# LoRa_Plug.net
KiCad netlist of a schematic drawn in EAGLE
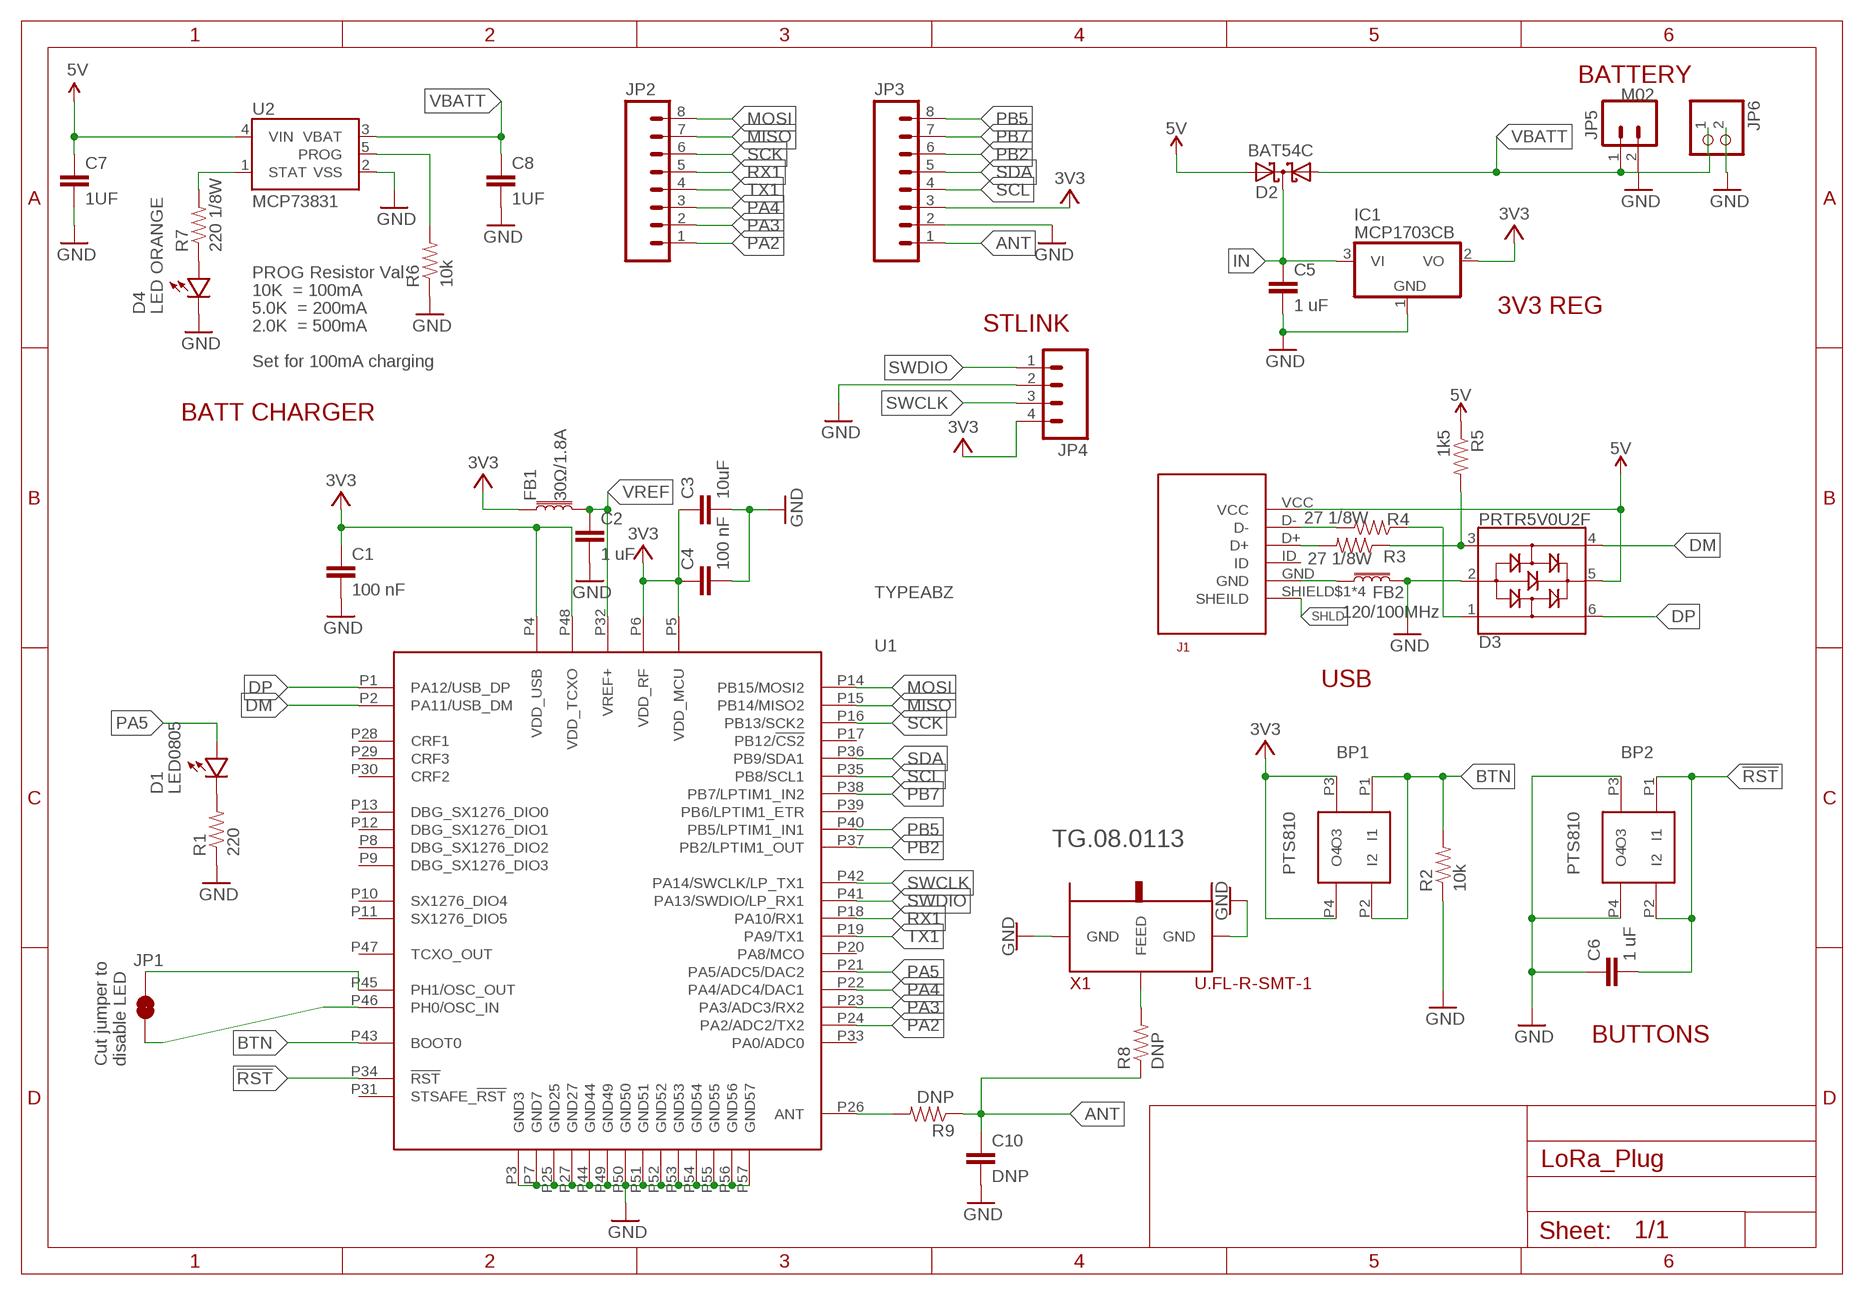
[diagram p0: schematic, sheet 1]

(export (version "E")
  (design (tool "Eeschema 10.0.6"))
  (components
    (comp (ref "BP1")
      (value "PTS810")
      (footprint "eagle-import:C&KTACTILESWITCH")
      (libsource (lib "eagle-import") (part "C&KTACTILESWITCH"))
    )
    (comp (ref "BP2")
      (value "PTS810")
      (footprint "eagle-import:C&KTACTILESWITCH")
      (libsource (lib "eagle-import") (part "C&KTACTILESWITCH"))
    )
    (comp (ref "C1")
      (value "100 nF")
      (footprint "eagle-import:0603-CAP")
      (libsource (lib "eagle-import") (part "CAP0603-CAP"))
    )
    (comp (ref "C2")
      (value "1 uF")
      (footprint "eagle-import:0603-CAP")
      (libsource (lib "eagle-import") (part "CAP0603-CAP"))
    )
    (comp (ref "C3")
      (value "10uF")
      (footprint "eagle-import:0603-CAP")
      (libsource (lib "eagle-import") (part "CAP0603-CAP"))
    )
    (comp (ref "C4")
      (value "100 nF")
      (footprint "eagle-import:0603-CAP")
      (libsource (lib "eagle-import") (part "CAP0603-CAP"))
    )
    (comp (ref "C5")
      (value "1 uF")
      (footprint "eagle-import:0603-CAP")
      (libsource (lib "eagle-import") (part "CAP0603-CAP"))
    )
    (comp (ref "C6")
      (value "1 uF")
      (footprint "eagle-import:0603-CAP")
      (libsource (lib "eagle-import") (part "CAP0603-CAP"))
    )
    (comp (ref "C7")
      (value "1UF")
      (footprint "eagle-import:0603-CAP")
      (libsource (lib "eagle-import") (part "CAP0603-CAP"))
    )
    (comp (ref "C8")
      (value "1UF")
      (footprint "eagle-import:0603-CAP")
      (libsource (lib "eagle-import") (part "CAP0603-CAP"))
    )
    (comp (ref "C10")
      (value "DNP")
      (footprint "eagle-import:0603-CAP")
      (libsource (lib "eagle-import") (part "CAP0603-CAP"))
    )
    (comp (ref "D1")
      (value "LED0805")
      (footprint "eagle-import:0805-LED")
      (libsource (lib "eagle-import") (part "LED0805"))
    )
    (comp (ref "D2")
      (value "BAT54C")
      (footprint "eagle-import:SOT23")
      (libsource (lib "eagle-import") (part "BAT54C"))
    )
    (comp (ref "D3")
      (value "PRTR5V0U2F")
      (footprint "eagle-import:SOT886")
      (libsource (lib "eagle-import") (part "PRTR5V0U2F"))
    )
    (comp (ref "D4")
      (value "LED ORANGE")
      (footprint "eagle-import:0805-LED")
      (libsource (lib "eagle-import") (part "LED0805"))
    )
    (comp (ref "FB1")
      (value "30Ω/1.8A")
      (footprint "eagle-import:0603")
      (libsource (lib "eagle-import") (part "FERRITE_BEAD-0603"))
    )
    (comp (ref "FB2")
      (value "120/100MHz")
      (footprint "eagle-import:0603")
      (libsource (lib "eagle-import") (part "FERRITE_BEAD-0603"))
    )
    (comp (ref "IC1")
      (value "MCP1703CB")
      (footprint "eagle-import:SOT23")
      (libsource (lib "eagle-import") (part "MCP1703CB"))
    )
    (comp (ref "J1")
      (value "10118193-0001LF")
      (footprint "eagle-import:10118193-0001LF")
      (libsource (lib "eagle-import") (part "10118193-0001LF"))
    )
    (comp (ref "JP1")
      (value "JUMPER-SMT_2_NC_TRACE_SILK")
      (footprint "eagle-import:SMT-JUMPER_2_NC_TRACE_SILK")
      (libsource (lib "eagle-import") (part "JUMPER-SMT_2_NC_TRACE_SILK"))
    )
    (comp (ref "JP2")
      (value "M08")
      (footprint "eagle-import:1X08")
      (libsource (lib "eagle-import") (part "M08"))
    )
    (comp (ref "JP3")
      (value "M08")
      (footprint "eagle-import:1X08")
      (libsource (lib "eagle-import") (part "M08"))
    )
    (comp (ref "JP4")
      (value "M04PTH")
      (footprint "eagle-import:1X04")
      (libsource (lib "eagle-import") (part "M04PTH"))
    )
    (comp (ref "JP5")
      (value "M02")
      (footprint "eagle-import:1X02")
      (libsource (lib "eagle-import") (part "M02"))
    )
    (comp (ref "JP6")
      (value "JST_2PIN-THM")
      (footprint "eagle-import:JST-PH-2-THM")
      (libsource (lib "eagle-import") (part "JST_2PIN-THM"))
    )
    (comp (ref "R1")
      (value "220")
      (footprint "eagle-import:0603-RES")
      (libsource (lib "eagle-import") (part "RESISTOR0603-RES"))
    )
    (comp (ref "R2")
      (value "10k")
      (footprint "eagle-import:0603-RES")
      (libsource (lib "eagle-import") (part "RESISTOR0603-RES"))
    )
    (comp (ref "R3")
      (value "27 1/8W")
      (footprint "eagle-import:0603-RES")
      (libsource (lib "eagle-import") (part "RESISTOR0603-RES"))
    )
    (comp (ref "R4")
      (value "27 1/8W")
      (footprint "eagle-import:0603-RES")
      (libsource (lib "eagle-import") (part "RESISTOR0603-RES"))
    )
    (comp (ref "R5")
      (value "1k5")
      (footprint "eagle-import:0603-RES")
      (libsource (lib "eagle-import") (part "RESISTOR0603-RES"))
    )
    (comp (ref "R6")
      (value "10k")
      (footprint "eagle-import:0603-RES")
      (libsource (lib "eagle-import") (part "RESISTOR0603-RES"))
    )
    (comp (ref "R7")
      (value "220 1/8W")
      (footprint "eagle-import:0805")
      (libsource (lib "eagle-import") (part "RESISTOR0805"))
    )
    (comp (ref "R8")
      (value "DNP")
      (footprint "eagle-import:0603-RES")
      (libsource (lib "eagle-import") (part "RESISTOR0603-RES"))
    )
    (comp (ref "R9")
      (value "DNP")
      (footprint "eagle-import:0603-RES")
      (libsource (lib "eagle-import") (part "RESISTOR0603-RES"))
    )
    (comp (ref "U1")
      (value "TYPEABZ")
      (footprint "eagle-import:TYPEABZ")
      (libsource (lib "eagle-import") (part "TYPEABZ"))
    )
    (comp (ref "U2")
      (value "MCP73831")
      (footprint "eagle-import:SOT23-5_1")
      (libsource (lib "eagle-import") (part "MCP73831"))
    )
    (comp (ref "X1")
      (value "U.FL-R-SMT-1")
      (footprint "eagle-import:U.FL-R-SMT-1")
      (libsource (lib "eagle-import") (part "U.FL-R-SMT-1"))
    )
  )
  (nets
    (net (code "1") (name "/~{RST}") (class "Default")
      (node (ref "BP2") (pin "P1") (pinfunction "I1_P1") (pintype "bidirectional"))
      (node (ref "BP2") (pin "P2") (pinfunction "I2_P2") (pintype "bidirectional"))
      (node (ref "C6") (pin "2") (pinfunction "2_2") (pintype "passive"))
      (node (ref "U1") (pin "P34") (pinfunction "~{RST}_P34") (pintype "bidirectional"))
    )
    (net (code "2") (name "3V3") (class "Default")
      (node (ref "BP1") (pin "P3") (pinfunction "O3_P3") (pintype "bidirectional"))
      (node (ref "BP1") (pin "P4") (pinfunction "O4_P4") (pintype "bidirectional"))
      (node (ref "C1") (pin "1") (pinfunction "1_1") (pintype "passive"))
      (node (ref "C3") (pin "1") (pinfunction "1_1") (pintype "passive"))
      (node (ref "C4") (pin "1") (pinfunction "1_1") (pintype "passive"))
      (node (ref "FB1") (pin "1") (pinfunction "1_1") (pintype "passive"))
      (node (ref "IC1") (pin "2") (pinfunction "VO_2") (pintype "passive"))
      (node (ref "JP3") (pin "3") (pinfunction "3_3") (pintype "passive"))
      (node (ref "JP4") (pin "4") (pinfunction "4_4") (pintype "passive"))
      (node (ref "U1") (pin "P4") (pinfunction "VDD_USB_P4") (pintype "power_in"))
      (node (ref "U1") (pin "P48") (pinfunction "VDD_TCXO_P48") (pintype "power_in"))
      (node (ref "U1") (pin "P5") (pinfunction "VDD_MCU_P5") (pintype "power_in"))
      (node (ref "U1") (pin "P6") (pinfunction "VDD_RF_P6") (pintype "power_in"))
    )
    (net (code "3") (name "5V") (class "Default")
      (node (ref "C7") (pin "1") (pinfunction "1_1") (pintype "passive"))
      (node (ref "D2") (pin "2") (pinfunction "A2_2") (pintype "passive"))
      (node (ref "D3") (pin "5") (pinfunction "5_5") (pintype "bidirectional"))
      (node (ref "J1") (pin "VCC") (pinfunction "VCC_VCC") (pintype "bidirectional"))
      (node (ref "R5") (pin "1") (pinfunction "1_1") (pintype "passive"))
      (node (ref "U2") (pin "4") (pinfunction "VIN_4") (pintype "power_in"))
    )
    (net (code "4") (name "ANT") (class "Default")
      (node (ref "C10") (pin "1") (pinfunction "1_1") (pintype "passive"))
      (node (ref "JP3") (pin "1") (pinfunction "1_1") (pintype "passive"))
      (node (ref "R8") (pin "1") (pinfunction "1_1") (pintype "passive"))
      (node (ref "R9") (pin "1") (pinfunction "1_1") (pintype "passive"))
    )
    (net (code "5") (name "BTN") (class "Default")
      (node (ref "BP1") (pin "P1") (pinfunction "I1_P1") (pintype "bidirectional"))
      (node (ref "BP1") (pin "P2") (pinfunction "I2_P2") (pintype "bidirectional"))
      (node (ref "R2") (pin "2") (pinfunction "2_2") (pintype "passive"))
      (node (ref "U1") (pin "P43") (pinfunction "BOOT0_P43") (pintype "bidirectional"))
    )
    (net (code "6") (name "DM") (class "Default")
      (node (ref "D3") (pin "4") (pinfunction "4_4") (pintype "bidirectional"))
      (node (ref "U1") (pin "P2") (pinfunction "PA11/USB_DM_P2") (pintype "bidirectional"))
    )
    (net (code "7") (name "DP") (class "Default")
      (node (ref "D3") (pin "6") (pinfunction "6_6") (pintype "bidirectional"))
      (node (ref "U1") (pin "P1") (pinfunction "PA12/USB_DP_P1") (pintype "bidirectional"))
    )
    (net (code "8") (name "GND") (class "Default")
      (node (ref "BP2") (pin "P3") (pinfunction "O3_P3") (pintype "bidirectional"))
      (node (ref "BP2") (pin "P4") (pinfunction "O4_P4") (pintype "bidirectional"))
      (node (ref "C1") (pin "2") (pinfunction "2_2") (pintype "passive"))
      (node (ref "C10") (pin "2") (pinfunction "2_2") (pintype "passive"))
      (node (ref "C2") (pin "2") (pinfunction "2_2") (pintype "passive"))
      (node (ref "C3") (pin "2") (pinfunction "2_2") (pintype "passive"))
      (node (ref "C4") (pin "2") (pinfunction "2_2") (pintype "passive"))
      (node (ref "C5") (pin "2") (pinfunction "2_2") (pintype "passive"))
      (node (ref "C6") (pin "1") (pinfunction "1_1") (pintype "passive"))
      (node (ref "C7") (pin "2") (pinfunction "2_2") (pintype "passive"))
      (node (ref "C8") (pin "2") (pinfunction "2_2") (pintype "passive"))
      (node (ref "D3") (pin "2") (pinfunction "2_2") (pintype "bidirectional"))
      (node (ref "D4") (pin "MINUS") (pinfunction "MINUS_MINUS") (pintype "passive"))
      (node (ref "FB2") (pin "2") (pinfunction "2_2") (pintype "passive"))
      (node (ref "IC1") (pin "1") (pinfunction "GND_1") (pintype "passive"))
      (node (ref "JP3") (pin "2") (pinfunction "2_2") (pintype "passive"))
      (node (ref "JP4") (pin "2") (pinfunction "2_2") (pintype "passive"))
      (node (ref "JP5") (pin "2") (pinfunction "2_2") (pintype "passive"))
      (node (ref "JP6") (pin "2") (pinfunction "1_2") (pintype "passive"))
      (node (ref "R1") (pin "1") (pinfunction "1_1") (pintype "passive"))
      (node (ref "R2") (pin "1") (pinfunction "1_1") (pintype "passive"))
      (node (ref "R6") (pin "1") (pinfunction "1_1") (pintype "passive"))
      (node (ref "U1") (pin "P25") (pinfunction "GND25_P25") (pintype "power_in"))
      (node (ref "U1") (pin "P27") (pinfunction "GND27_P27") (pintype "power_in"))
      (node (ref "U1") (pin "P3") (pinfunction "GND3_P3") (pintype "power_in"))
      (node (ref "U1") (pin "P44") (pinfunction "GND44_P44") (pintype "power_in"))
      (node (ref "U1") (pin "P49") (pinfunction "GND49_P49") (pintype "power_in"))
      (node (ref "U1") (pin "P50") (pinfunction "GND50_P50") (pintype "power_in"))
      (node (ref "U1") (pin "P51") (pinfunction "GND51_P51") (pintype "power_in"))
      (node (ref "U1") (pin "P52") (pinfunction "GND52_P52") (pintype "power_in"))
      (node (ref "U1") (pin "P53") (pinfunction "GND53_P53") (pintype "power_in"))
      (node (ref "U1") (pin "P54") (pinfunction "GND54_P54") (pintype "power_in"))
      (node (ref "U1") (pin "P55") (pinfunction "GND55_P55") (pintype "power_in"))
      (node (ref "U1") (pin "P56") (pinfunction "GND56_P56") (pintype "power_in"))
      (node (ref "U1") (pin "P57") (pinfunction "GND57_P57") (pintype "power_in"))
      (node (ref "U1") (pin "P7") (pinfunction "GND7_P7") (pintype "power_in"))
      (node (ref "U2") (pin "2") (pinfunction "VSS_2") (pintype "power_in"))
      (node (ref "X1") (pin "P$1") (pinfunction "GND_P$1") (pintype "power_in"))
      (node (ref "X1") (pin "P$2") (pinfunction "GND_P$2") (pintype "power_in"))
    )
    (net (code "9") (name "IN") (class "Default")
      (node (ref "C5") (pin "1") (pinfunction "1_1") (pintype "passive"))
      (node (ref "D2") (pin "3") (pinfunction "CC_3") (pintype "passive"))
      (node (ref "IC1") (pin "3") (pinfunction "VI_3") (pintype "input"))
    )
    (net (code "10") (name "MISO") (class "Default")
      (node (ref "JP2") (pin "7") (pinfunction "7_7") (pintype "passive"))
      (node (ref "U1") (pin "P15") (pinfunction "PB14/MISO2_P15") (pintype "bidirectional"))
    )
    (net (code "11") (name "MOSI") (class "Default")
      (node (ref "JP2") (pin "8") (pinfunction "8_8") (pintype "passive"))
      (node (ref "U1") (pin "P14") (pinfunction "PB15/MOSI2_P14") (pintype "bidirectional"))
    )
    (net (code "12") (name "Net-(D1-PadMINUS)") (class "Default")
      (node (ref "D1") (pin "MINUS") (pinfunction "MINUS_MINUS") (pintype "passive"))
      (node (ref "R1") (pin "2") (pinfunction "2_2") (pintype "passive"))
    )
    (net (code "13") (name "Net-(D3-Pad1)") (class "Default")
      (node (ref "D3") (pin "1") (pinfunction "1_1") (pintype "bidirectional"))
      (node (ref "R4") (pin "1") (pinfunction "1_1") (pintype "passive"))
    )
    (net (code "14") (name "Net-(D3-Pad3)") (class "Default")
      (node (ref "D3") (pin "3") (pinfunction "3_3") (pintype "bidirectional"))
      (node (ref "R3") (pin "1") (pinfunction "1_1") (pintype "passive"))
      (node (ref "R5") (pin "2") (pinfunction "2_2") (pintype "passive"))
    )
    (net (code "15") (name "Net-(D4-PadPLUS)") (class "Default")
      (node (ref "D4") (pin "PLUS") (pinfunction "PLUS_PLUS") (pintype "passive"))
      (node (ref "R7") (pin "1") (pinfunction "1_1") (pintype "passive"))
    )
    (net (code "16") (name "Net-(FB2-Pad1)") (class "Default")
      (node (ref "FB2") (pin "1") (pinfunction "1_1") (pintype "passive"))
      (node (ref "J1") (pin "GND") (pinfunction "GND_GND") (pintype "bidirectional"))
    )
    (net (code "17") (name "Net-(J1-PadD+)") (class "Default")
      (node (ref "J1") (pin "D+") (pinfunction "D+_D+") (pintype "bidirectional"))
      (node (ref "R3") (pin "2") (pinfunction "2_2") (pintype "passive"))
    )
    (net (code "18") (name "Net-(J1-PadD-)") (class "Default")
      (node (ref "J1") (pin "D-") (pinfunction "D-_D-") (pintype "bidirectional"))
      (node (ref "R4") (pin "2") (pinfunction "2_2") (pintype "passive"))
    )
    (net (code "19") (name "Net-(U1-ANT)") (class "Default")
      (node (ref "R9") (pin "2") (pinfunction "2_2") (pintype "passive"))
      (node (ref "U1") (pin "P26") (pinfunction "ANT_P26") (pintype "bidirectional"))
    )
    (net (code "20") (name "Net-(U1-PH0{slash}OSC_IN)") (class "Default")
      (node (ref "JP1") (pin "1") (pinfunction "1_1") (pintype "passive"))
      (node (ref "U1") (pin "P46") (pinfunction "PH0/OSC_IN_P46") (pintype "bidirectional"))
    )
    (net (code "21") (name "Net-(U1-PH1{slash}OSC_OUT)") (class "Default")
      (node (ref "JP1") (pin "2") (pinfunction "2_2") (pintype "passive"))
      (node (ref "U1") (pin "P45") (pinfunction "PH1/OSC_OUT_P45") (pintype "bidirectional"))
    )
    (net (code "22") (name "Net-(U2-PROG)") (class "Default")
      (node (ref "R6") (pin "2") (pinfunction "2_2") (pintype "passive"))
      (node (ref "U2") (pin "5") (pinfunction "PROG_5") (pintype "input"))
    )
    (net (code "23") (name "Net-(U2-STAT)") (class "Default")
      (node (ref "R7") (pin "2") (pinfunction "2_2") (pintype "passive"))
      (node (ref "U2") (pin "1") (pinfunction "STAT_1") (pintype "output"))
    )
    (net (code "24") (name "Net-(X1-FEED)") (class "Default")
      (node (ref "R8") (pin "2") (pinfunction "2_2") (pintype "passive"))
      (node (ref "X1") (pin "P$3") (pinfunction "FEED_P$3") (pintype "bidirectional"))
    )
    (net (code "25") (name "PA2") (class "Default")
      (node (ref "JP2") (pin "1") (pinfunction "1_1") (pintype "passive"))
      (node (ref "U1") (pin "P24") (pinfunction "PA2/ADC2/TX2_P24") (pintype "bidirectional"))
    )
    (net (code "26") (name "PA3") (class "Default")
      (node (ref "JP2") (pin "2") (pinfunction "2_2") (pintype "passive"))
      (node (ref "U1") (pin "P23") (pinfunction "PA3/ADC3/RX2_P23") (pintype "bidirectional"))
    )
    (net (code "27") (name "PA4") (class "Default")
      (node (ref "JP2") (pin "3") (pinfunction "3_3") (pintype "passive"))
      (node (ref "U1") (pin "P22") (pinfunction "PA4/ADC4/DAC1_P22") (pintype "bidirectional"))
    )
    (net (code "28") (name "PA5") (class "Default")
      (node (ref "D1") (pin "PLUS") (pinfunction "PLUS_PLUS") (pintype "passive"))
      (node (ref "U1") (pin "P21") (pinfunction "PA5/ADC5/DAC2_P21") (pintype "bidirectional"))
    )
    (net (code "29") (name "PB2") (class "Default")
      (node (ref "JP3") (pin "6") (pinfunction "6_6") (pintype "passive"))
      (node (ref "U1") (pin "P37") (pinfunction "PB2/LPTIM1_OUT_P37") (pintype "bidirectional"))
    )
    (net (code "30") (name "PB5") (class "Default")
      (node (ref "JP3") (pin "8") (pinfunction "8_8") (pintype "passive"))
      (node (ref "U1") (pin "P40") (pinfunction "PB5/LPTIM1_IN1_P40") (pintype "bidirectional"))
    )
    (net (code "31") (name "PB7") (class "Default")
      (node (ref "JP3") (pin "7") (pinfunction "7_7") (pintype "passive"))
      (node (ref "U1") (pin "P38") (pinfunction "PB7/LPTIM1_IN2_P38") (pintype "bidirectional"))
    )
    (net (code "32") (name "RX1") (class "Default")
      (node (ref "JP2") (pin "5") (pinfunction "5_5") (pintype "passive"))
      (node (ref "U1") (pin "P18") (pinfunction "PA10/RX1_P18") (pintype "bidirectional"))
    )
    (net (code "33") (name "SCK") (class "Default")
      (node (ref "JP2") (pin "6") (pinfunction "6_6") (pintype "passive"))
      (node (ref "U1") (pin "P16") (pinfunction "PB13/SCK2_P16") (pintype "bidirectional"))
    )
    (net (code "34") (name "SCL") (class "Default")
      (node (ref "JP3") (pin "4") (pinfunction "4_4") (pintype "passive"))
      (node (ref "U1") (pin "P35") (pinfunction "PB8/SCL1_P35") (pintype "bidirectional"))
    )
    (net (code "35") (name "SDA") (class "Default")
      (node (ref "JP3") (pin "5") (pinfunction "5_5") (pintype "passive"))
      (node (ref "U1") (pin "P36") (pinfunction "PB9/SDA1_P36") (pintype "bidirectional"))
    )
    (net (code "36") (name "SHLD") (class "Default")
      (node (ref "J1") (pin "SHIELD$1") (pinfunction "SHEILD_SHIELD$1") (pintype "bidirectional"))
      (node (ref "J1") (pin "SHIELD$2") (pinfunction "SHEILD_SHIELD$2") (pintype "bidirectional"))
      (node (ref "J1") (pin "SHIELD$3") (pinfunction "SHEILD_SHIELD$3") (pintype "bidirectional"))
      (node (ref "J1") (pin "SHIELD$4") (pinfunction "SHEILD_SHIELD$4") (pintype "bidirectional"))
    )
    (net (code "37") (name "SWCLK") (class "Default")
      (node (ref "JP4") (pin "3") (pinfunction "3_3") (pintype "passive"))
      (node (ref "U1") (pin "P42") (pinfunction "PA14/SWCLK/LP_TX1_P42") (pintype "bidirectional"))
    )
    (net (code "38") (name "SWDIO") (class "Default")
      (node (ref "JP4") (pin "1") (pinfunction "1_1") (pintype "passive"))
      (node (ref "U1") (pin "P41") (pinfunction "PA13/SWDIO/LP_RX1_P41") (pintype "bidirectional"))
    )
    (net (code "39") (name "TX1") (class "Default")
      (node (ref "JP2") (pin "4") (pinfunction "4_4") (pintype "passive"))
      (node (ref "U1") (pin "P19") (pinfunction "PA9/TX1_P19") (pintype "bidirectional"))
    )
    (net (code "40") (name "VBATT") (class "Default")
      (node (ref "C8") (pin "1") (pinfunction "1_1") (pintype "passive"))
      (node (ref "D2") (pin "1") (pinfunction "A1_1") (pintype "passive"))
      (node (ref "JP5") (pin "1") (pinfunction "1_1") (pintype "passive"))
      (node (ref "JP6") (pin "1") (pinfunction "2_1") (pintype "passive"))
      (node (ref "U2") (pin "3") (pinfunction "VBAT_3") (pintype "power_in"))
    )
    (net (code "41") (name "VREF") (class "Default")
      (node (ref "C2") (pin "1") (pinfunction "1_1") (pintype "passive"))
      (node (ref "FB1") (pin "2") (pinfunction "2_2") (pintype "passive"))
      (node (ref "U1") (pin "P32") (pinfunction "VREF+_P32") (pintype "power_in"))
    )
    (net (code "42") (name "unconnected-(J1-PadID)") (class "Default")
      (node (ref "J1") (pin "ID") (pinfunction "ID_ID") (pintype "bidirectional"))
    )
    (net (code "43") (name "unconnected-(U1-CRF1-PadP28)") (class "Default")
      (node (ref "U1") (pin "P28") (pinfunction "CRF1_P28") (pintype "no_connect"))
    )
    (net (code "44") (name "unconnected-(U1-CRF2-PadP30)") (class "Default")
      (node (ref "U1") (pin "P30") (pinfunction "CRF2_P30") (pintype "no_connect"))
    )
    (net (code "45") (name "unconnected-(U1-CRF3-PadP29)") (class "Default")
      (node (ref "U1") (pin "P29") (pinfunction "CRF3_P29") (pintype "no_connect"))
    )
    (net (code "46") (name "unconnected-(U1-DBG_SX1276_DIO0-PadP13)") (class "Default")
      (node (ref "U1") (pin "P13") (pinfunction "DBG_SX1276_DIO0_P13") (pintype "no_connect"))
    )
    (net (code "47") (name "unconnected-(U1-DBG_SX1276_DIO1-PadP12)") (class "Default")
      (node (ref "U1") (pin "P12") (pinfunction "DBG_SX1276_DIO1_P12") (pintype "no_connect"))
    )
    (net (code "48") (name "unconnected-(U1-DBG_SX1276_DIO2-PadP8)") (class "Default")
      (node (ref "U1") (pin "P8") (pinfunction "DBG_SX1276_DIO2_P8") (pintype "no_connect"))
    )
    (net (code "49") (name "unconnected-(U1-DBG_SX1276_DIO3-PadP9)") (class "Default")
      (node (ref "U1") (pin "P9") (pinfunction "DBG_SX1276_DIO3_P9") (pintype "no_connect"))
    )
    (net (code "50") (name "unconnected-(U1-PA0{slash}ADC0-PadP33)") (class "Default")
      (node (ref "U1") (pin "P33") (pinfunction "PA0/ADC0_P33") (pintype "bidirectional"))
    )
    (net (code "51") (name "unconnected-(U1-PA8{slash}MCO-PadP20)") (class "Default")
      (node (ref "U1") (pin "P20") (pinfunction "PA8/MCO_P20") (pintype "bidirectional"))
    )
    (net (code "52") (name "unconnected-(U1-PB6{slash}LPTIM1_ETR-PadP39)") (class "Default")
      (node (ref "U1") (pin "P39") (pinfunction "PB6/LPTIM1_ETR_P39") (pintype "bidirectional"))
    )
    (net (code "53") (name "unconnected-(U1-PB12{slash}~{CS2}-PadP17)") (class "Default")
      (node (ref "U1") (pin "P17") (pinfunction "PB12/~{CS2}_P17") (pintype "bidirectional"))
    )
    (net (code "54") (name "unconnected-(U1-STSAFE_~{RST}-PadP31)") (class "Default")
      (node (ref "U1") (pin "P31") (pinfunction "STSAFE_~{RST}_P31") (pintype "bidirectional"))
    )
    (net (code "55") (name "unconnected-(U1-SX1276_DIO4-PadP10)") (class "Default")
      (node (ref "U1") (pin "P10") (pinfunction "SX1276_DIO4_P10") (pintype "bidirectional"))
    )
    (net (code "56") (name "unconnected-(U1-SX1276_DIO5-PadP11)") (class "Default")
      (node (ref "U1") (pin "P11") (pinfunction "SX1276_DIO5_P11") (pintype "bidirectional"))
    )
    (net (code "57") (name "unconnected-(U1-TCXO_OUT-PadP47)") (class "Default")
      (node (ref "U1") (pin "P47") (pinfunction "TCXO_OUT_P47") (pintype "bidirectional"))
    )
  )
)
